# Motion_Controller.net
KiCad netlist of a schematic drawn in Altium Designer
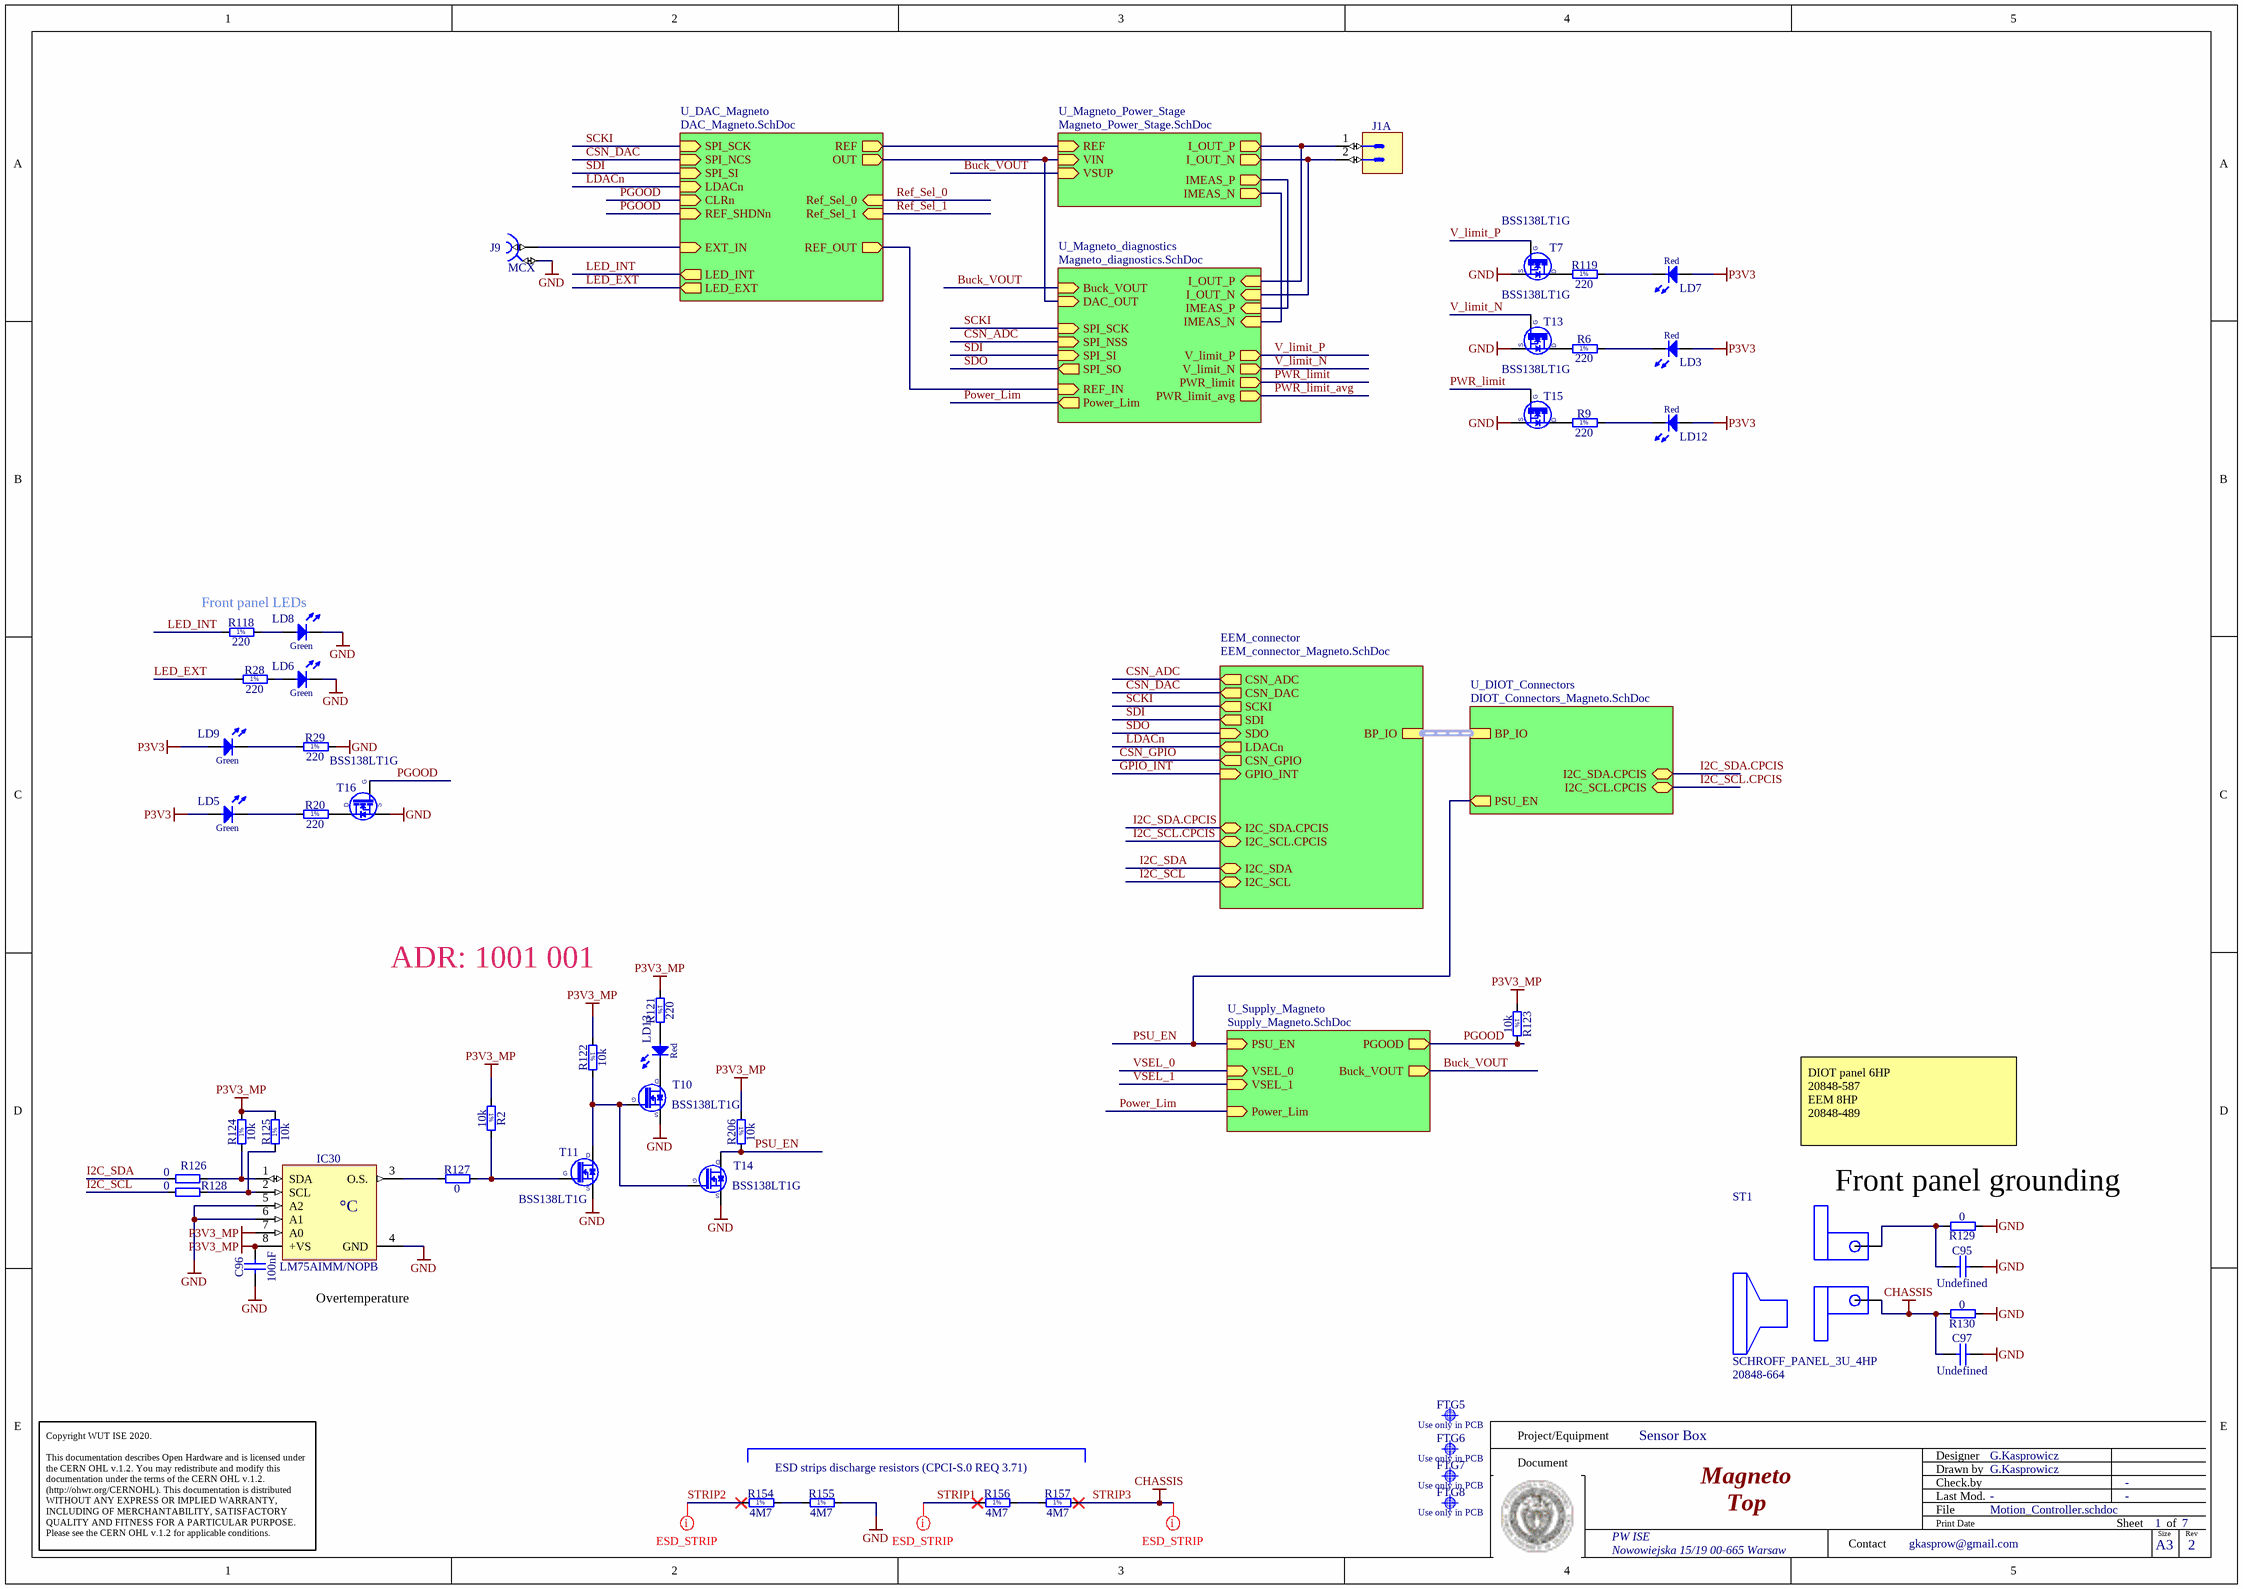
[diagram p0: Motion_Controller.schdoc]

(export (version "E")
  (design (tool "Eeschema 10.0.6"))
  (components
    (comp (ref "C95")
      (value "Undefined")
      (footprint "CAPC2012X135N")
      (description "Non-polarised capacitor")
      (fields (field (name "PART NUMBER") "CC0805_NO-VALUE") (field (name "AUTHOR") "CERN DEM JLC"))
      (libsource (lib "Capacitors") (part "Capacitor - non polarized"))
    )
    (comp (ref "C96")
      (value "100nF")
      (footprint "CAPC1005X55N")
      (description "Non-polarised capacitor")
      (fields
        (field (name "PART NUMBER") "CC0402_100NF_16V_10%_X5R")
        (field (name "VOLTAGE") "16V")
        (field (name "AUTHOR") "CERN DEM JLC")
      )
      (libsource (lib "Capacitors") (part "Capacitor - non polarized"))
    )
    (comp (ref "C97")
      (value "Undefined")
      (footprint "CAPC2012X135N")
      (description "Non-polarised capacitor")
      (fields (field (name "PART NUMBER") "CC0805_NO-VALUE") (field (name "AUTHOR") "CERN DEM JLC"))
      (libsource (lib "Capacitors") (part "Capacitor - non polarized"))
    )
    (comp (ref "FTG5")
      (value "Use only in PCB")
      (footprint "FIDUCIAL_TOP_C100-200")
      (description "Fiducial Target")
      (fields (field (name "PART NUMBER") "FIDUCIAL_TARGET_C100-200") (field (name "AUTHOR") "CERN DEM JLC"))
      (libsource (lib "Eletro-mechanical") (part "Fiducial Target"))
    )
    (comp (ref "FTG6")
      (value "Use only in PCB")
      (footprint "FIDUCIAL_TOP_S100-200")
      (description "Fiducial Target")
      (fields (field (name "PART NUMBER") "FIDUCIAL_TARGET_S100-200") (field (name "AUTHOR") "CERN DEM JLC"))
      (libsource (lib "Eletro-mechanical") (part "Fiducial Target"))
    )
    (comp (ref "FTG7")
      (value "Use only in PCB")
      (footprint "FIDUCIAL_TOP_S100-200")
      (description "Fiducial Target")
      (fields (field (name "PART NUMBER") "FIDUCIAL_TARGET_S100-200") (field (name "AUTHOR") "CERN DEM JLC"))
      (libsource (lib "Eletro-mechanical") (part "Fiducial Target"))
    )
    (comp (ref "FTG8")
      (value "Use only in PCB")
      (footprint "FIDUCIAL_TOP_S100-200")
      (description "Fiducial Target")
      (fields (field (name "PART NUMBER") "FIDUCIAL_TARGET_S100-200") (field (name "AUTHOR") "CERN DEM JLC"))
      (libsource (lib "Eletro-mechanical") (part "Fiducial Target"))
    )
    (comp (ref "IC30")
      (value "LM75AIMM/NOPB")
      (footprint "SOP65P490X109-8N")
      (description "Digital Temperature Sensor and Thermal Watchdog with Two-Wire Interface")
      (fields (field (name "MANUFACTURER") "TEXAS INSTRUMENTS") (field (name "AUTHOR") "CERN DEM JLC"))
      (libsource (lib "ICs And Semiconductors") (part "LM75"))
    )
    (comp (ref "J1")
      (value "~")
      (footprint "PHOENIX_1817615")
      (description "Connector 2 Male+2MTG")
      (fields
        (field (name "PART NUMBER") "PHOENIX_1817615")
        (field (name "MANUFACTURER") "PHOENIX CONTACT")
        (field (name "AUTHOR") "CERN DEM BC")
      )
      (libsource (lib "Connectors") (part "Connector 2 Male+2MTG"))
    )
    (comp (ref "J9")
      (value "MCX")
      (footprint "AMPHENOL_919-383J-51A")
      (fields
        (field (name "PART NUMBER") "AMPHENOL_919-383J-51A")
        (field (name "MANUFACTURER") "AMPHENOL")
        (field (name "MANUFACTURER PART NUMBER") "919-383J-51A")
        (field (name "AUTHOR") "CERN DEM BC")
      )
      (libsource (lib "Connectors") (part "Coax_1Female_1Shield"))
    )
    (comp (ref "LD3")
      (value "Red")
      (footprint "LED_DIALIGHT_555-200")
      (description "LED Red 1C 2A")
      (fields
        (field (name "PART NUMBER") "LED_DIALIGHT_555-2001F")
        (field (name "MANUFACTURER") "DIALIGHT")
        (field (name "AUTHOR") "CERN DEM JMW")
      )
      (libsource (lib "ICs And Semiconductors") (part "LED Red 1C 2A"))
    )
    (comp (ref "LD5")
      (value "Green")
      (footprint "LED_DIALIGHT_555-230")
      (description "LED Green 1C 2A")
      (fields
        (field (name "PART NUMBER") "LED_DIALIGHT_555-2301F")
        (field (name "MANUFACTURER") "DIALIGHT")
        (field (name "AUTHOR") "CERN DEM JMW")
      )
      (libsource (lib "ICs And Semiconductors") (part "LED Green 1C 2A"))
    )
    (comp (ref "LD6")
      (value "Green")
      (footprint "LED_DIALIGHT_555-230")
      (description "LED Green 1C 2A")
      (fields
        (field (name "PART NUMBER") "LED_DIALIGHT_555-2301F")
        (field (name "MANUFACTURER") "DIALIGHT")
        (field (name "AUTHOR") "CERN DEM JMW")
      )
      (libsource (lib "ICs And Semiconductors") (part "LED Green 1C 2A"))
    )
    (comp (ref "LD7")
      (value "Red")
      (footprint "LED_DIALIGHT_555-200")
      (description "LED Red 1C 2A")
      (fields
        (field (name "PART NUMBER") "LED_DIALIGHT_555-2001F")
        (field (name "MANUFACTURER") "DIALIGHT")
        (field (name "AUTHOR") "CERN DEM JMW")
      )
      (libsource (lib "ICs And Semiconductors") (part "LED Red 1C 2A"))
    )
    (comp (ref "LD8")
      (value "Green")
      (footprint "LED_DIALIGHT_555-230")
      (description "LED Green 1C 2A")
      (fields
        (field (name "PART NUMBER") "LED_DIALIGHT_555-2301F")
        (field (name "MANUFACTURER") "DIALIGHT")
        (field (name "AUTHOR") "CERN DEM JMW")
      )
      (libsource (lib "ICs And Semiconductors") (part "LED Green 1C 2A"))
    )
    (comp (ref "LD9")
      (value "Green")
      (footprint "LED_DIALIGHT_555-230")
      (description "LED Green 1C 2A")
      (fields
        (field (name "PART NUMBER") "LED_DIALIGHT_555-2301F")
        (field (name "MANUFACTURER") "DIALIGHT")
        (field (name "AUTHOR") "CERN DEM JMW")
      )
      (libsource (lib "ICs And Semiconductors") (part "LED Green 1C 2A"))
    )
    (comp (ref "LD12")
      (value "Red")
      (footprint "LED_DIALIGHT_555-200")
      (description "LED Red 1C 2A")
      (fields
        (field (name "PART NUMBER") "LED_DIALIGHT_555-2001F")
        (field (name "MANUFACTURER") "DIALIGHT")
        (field (name "AUTHOR") "CERN DEM JMW")
      )
      (libsource (lib "ICs And Semiconductors") (part "LED Red 1C 2A"))
    )
    (comp (ref "LD13")
      (value "Red")
      (footprint "LED_DIALIGHT_555-200")
      (description "LED Red 1C 2A")
      (fields
        (field (name "PART NUMBER") "LED_DIALIGHT_555-2001F")
        (field (name "MANUFACTURER") "DIALIGHT")
        (field (name "AUTHOR") "CERN DEM JMW")
      )
      (libsource (lib "ICs And Semiconductors") (part "LED Red 1C 2A"))
    )
    (comp (ref "R2")
      (value "10k")
      (footprint "RESC1005X40N")
      (description "Resistor - 1%")
      (fields
        (field (name "PART NUMBER") "R0402_10K_1%_0.0625W_100PPM")
        (field (name "POWER") "0.0625W")
        (field (name "AUTHOR") "CERN DEM JLC")
      )
      (libsource (lib "Resistors") (part "Resistor - 1%"))
    )
    (comp (ref "R6")
      (value "220")
      (footprint "RESC1608X55N")
      (description "Resistor - 1%")
      (fields
        (field (name "PART NUMBER") "R0603_220R_1%_0.1W_100PPM")
        (field (name "POWER") "0.1W")
        (field (name "AUTHOR") "CERN DEM JLC")
      )
      (libsource (lib "Resistors") (part "Resistor - 1%"))
    )
    (comp (ref "R9")
      (value "220")
      (footprint "RESC1608X55N")
      (description "Resistor - 1%")
      (fields
        (field (name "PART NUMBER") "R0603_220R_1%_0.1W_100PPM")
        (field (name "POWER") "0.1W")
        (field (name "AUTHOR") "CERN DEM JLC")
      )
      (libsource (lib "Resistors") (part "Resistor - 1%"))
    )
    (comp (ref "R20")
      (value "220")
      (footprint "RESC1608X55N")
      (description "Resistor - 1%")
      (fields
        (field (name "PART NUMBER") "R0603_220R_1%_0.1W_100PPM")
        (field (name "POWER") "0.1W")
        (field (name "AUTHOR") "CERN DEM JLC")
      )
      (libsource (lib "Resistors") (part "Resistor - 1%"))
    )
    (comp (ref "R28")
      (value "220")
      (footprint "RESC1608X55N")
      (description "Resistor - 1%")
      (fields
        (field (name "PART NUMBER") "R0603_220R_1%_0.1W_100PPM")
        (field (name "POWER") "0.1W")
        (field (name "AUTHOR") "CERN DEM JLC")
      )
      (libsource (lib "Resistors") (part "Resistor - 1%"))
    )
    (comp (ref "R29")
      (value "220")
      (footprint "RESC1608X55N")
      (description "Resistor - 1%")
      (fields
        (field (name "PART NUMBER") "R0603_220R_1%_0.1W_100PPM")
        (field (name "POWER") "0.1W")
        (field (name "AUTHOR") "CERN DEM JLC")
      )
      (libsource (lib "Resistors") (part "Resistor - 1%"))
    )
    (comp (ref "R118")
      (value "220")
      (footprint "RESC1608X55N")
      (description "Resistor - 1%")
      (fields
        (field (name "PART NUMBER") "R0603_220R_1%_0.1W_100PPM")
        (field (name "POWER") "0.1W")
        (field (name "AUTHOR") "CERN DEM JLC")
      )
      (libsource (lib "Resistors") (part "Resistor - 1%"))
    )
    (comp (ref "R119")
      (value "220")
      (footprint "RESC1608X55N")
      (description "Resistor - 1%")
      (fields
        (field (name "PART NUMBER") "R0603_220R_1%_0.1W_100PPM")
        (field (name "POWER") "0.1W")
        (field (name "AUTHOR") "CERN DEM JLC")
      )
      (libsource (lib "Resistors") (part "Resistor - 1%"))
    )
    (comp (ref "R121")
      (value "220")
      (footprint "RESC1608X55N")
      (description "Resistor - 1%")
      (fields
        (field (name "PART NUMBER") "R0603_220R_1%_0.1W_100PPM")
        (field (name "POWER") "0.1W")
        (field (name "AUTHOR") "CERN DEM JLC")
      )
      (libsource (lib "Resistors") (part "Resistor - 1%"))
    )
    (comp (ref "R122")
      (value "10k")
      (footprint "RESC1005X40N")
      (description "Resistor - 1%")
      (fields
        (field (name "PART NUMBER") "R0402_10K_1%_0.0625W_100PPM")
        (field (name "POWER") "0.0625W")
        (field (name "AUTHOR") "CERN DEM JLC")
      )
      (libsource (lib "Resistors") (part "Resistor - 1%"))
    )
    (comp (ref "R123")
      (value "10k")
      (footprint "RESC1005X40N")
      (description "Resistor - 1%")
      (fields
        (field (name "PART NUMBER") "R0402_10K_1%_0.0625W_100PPM")
        (field (name "POWER") "0.0625W")
        (field (name "AUTHOR") "CERN DEM JLC")
      )
      (libsource (lib "Resistors") (part "Resistor - 1%"))
    )
    (comp (ref "R124")
      (value "10k")
      (footprint "RESC1005X40N")
      (description "Resistor - 1%")
      (fields
        (field (name "PART NUMBER") "R0402_10K_1%_0.0625W_100PPM")
        (field (name "POWER") "0.0625W")
        (field (name "AUTHOR") "CERN DEM JLC")
      )
      (libsource (lib "Resistors") (part "Resistor - 1%"))
    )
    (comp (ref "R125")
      (value "10k")
      (footprint "RESC1005X40N")
      (description "Resistor - 1%")
      (fields
        (field (name "PART NUMBER") "R0402_10K_1%_0.0625W_100PPM")
        (field (name "POWER") "0.0625W")
        (field (name "AUTHOR") "CERN DEM JLC")
      )
      (libsource (lib "Resistors") (part "Resistor - 1%"))
    )
    (comp (ref "R126")
      (value "0")
      (footprint "RESC1005X40N")
      (description "Resistor")
      (fields
        (field (name "PART NUMBER") "R0402_0R_JUMPER")
        (field (name "MANUFACTURER") "GENERIC")
        (field (name "AUTHOR") "CERN DEM JLC")
      )
      (libsource (lib "Resistors") (part "Resistor"))
    )
    (comp (ref "R127")
      (value "0")
      (footprint "RESC1005X40N")
      (description "Resistor")
      (fields
        (field (name "PART NUMBER") "R0402_0R_JUMPER")
        (field (name "MANUFACTURER") "GENERIC")
        (field (name "AUTHOR") "CERN DEM JLC")
      )
      (libsource (lib "Resistors") (part "Resistor"))
    )
    (comp (ref "R128")
      (value "0")
      (footprint "RESC1005X40N")
      (description "Resistor")
      (fields
        (field (name "PART NUMBER") "R0402_0R_JUMPER")
        (field (name "MANUFACTURER") "GENERIC")
        (field (name "AUTHOR") "CERN DEM JLC")
      )
      (libsource (lib "Resistors") (part "Resistor"))
    )
    (comp (ref "R129")
      (value "0")
      (footprint "RESC1608X55N")
      (description "Resistor")
      (fields
        (field (name "PART NUMBER") "R0603_0R_JUMPER")
        (field (name "MANUFACTURER") "GENERIC")
        (field (name "AUTHOR") "CERN DEM JLC")
      )
      (libsource (lib "Resistors") (part "Resistor"))
    )
    (comp (ref "R130")
      (value "0")
      (footprint "RESC1608X55N")
      (description "Resistor")
      (fields
        (field (name "PART NUMBER") "R0603_0R_JUMPER")
        (field (name "MANUFACTURER") "GENERIC")
        (field (name "AUTHOR") "CERN DEM JLC")
      )
      (libsource (lib "Resistors") (part "Resistor"))
    )
    (comp (ref "R154")
      (value "4M7")
      (footprint "RESC2113X55N")
      (description "Resistor - 1%")
      (fields
        (field (name "PART NUMBER") "R0805_4M7_1%_0.125W_100PPM_VISHAY_CRCW e3")
        (field (name "POWER") "0.125W")
        (field (name "AUTHOR") "CERN DEM BR")
      )
      (libsource (lib "Resistors") (part "Resistor - 1%"))
    )
    (comp (ref "R155")
      (value "4M7")
      (footprint "RESC2113X55N")
      (description "Resistor - 1%")
      (fields
        (field (name "PART NUMBER") "R0805_4M7_1%_0.125W_100PPM_VISHAY_CRCW e3")
        (field (name "POWER") "0.125W")
        (field (name "AUTHOR") "CERN DEM BR")
      )
      (libsource (lib "Resistors") (part "Resistor - 1%"))
    )
    (comp (ref "R156")
      (value "4M7")
      (footprint "RESC2113X55N")
      (description "Resistor - 1%")
      (fields
        (field (name "PART NUMBER") "R0805_4M7_1%_0.125W_100PPM_VISHAY_CRCW e3")
        (field (name "POWER") "0.125W")
        (field (name "AUTHOR") "CERN DEM BR")
      )
      (libsource (lib "Resistors") (part "Resistor - 1%"))
    )
    (comp (ref "R157")
      (value "4M7")
      (footprint "RESC2113X55N")
      (description "Resistor - 1%")
      (fields
        (field (name "PART NUMBER") "R0805_4M7_1%_0.125W_100PPM_VISHAY_CRCW e3")
        (field (name "POWER") "0.125W")
        (field (name "AUTHOR") "CERN DEM BR")
      )
      (libsource (lib "Resistors") (part "Resistor - 1%"))
    )
    (comp (ref "R206")
      (value "10k")
      (footprint "RESC1005X40N")
      (description "Resistor - 1%")
      (fields
        (field (name "PART NUMBER") "R0402_10K_1%_0.0625W_100PPM")
        (field (name "POWER") "0.0625W")
        (field (name "AUTHOR") "CERN DEM JLC")
      )
      (libsource (lib "Resistors") (part "Resistor - 1%"))
    )
    (comp (ref "ST1")
      (value "SCHROFF_PANEL_3U_4HP")
      (footprint "SCHROFF_PANEL_3HP_4U")
      (description "Schroff 3HP 4U EUROCARD Panel Kit")
      (fields
        (field (name "MANUFACTURER") "Schroff")
        (field (name "MANUFACTURER PART NUMBER") "20818-017")
        (field (name "MANUFACTURER PART NUMBER 2") "20848-664")
      )
      (libsource (lib "Mechanical") (part "SCHROFF_PANEL_3U_4HP"))
    )
    (comp (ref "T7")
      (value "BSS138LT1G")
      (footprint "SOT95P240X110-3N")
      (description "N-CHANNEL MOSFET WITH DIODE")
      (fields (field (name "MANUFACTURER") "ON SEMICONDUCTOR") (field (name "AUTHOR") "CERN DEM JLC"))
      (libsource (lib "") (part "N-MOSFET-D 1G 2S 3D_1"))
    )
    (comp (ref "T10")
      (value "BSS138LT1G")
      (footprint "SOT95P240X110-3N")
      (description "N-CHANNEL MOSFET WITH DIODE")
      (fields (field (name "MANUFACTURER") "ON SEMICONDUCTOR") (field (name "AUTHOR") "CERN DEM JLC"))
      (libsource (lib "") (part "N-MOSFET-D 1G 2S 3D_2"))
    )
    (comp (ref "T11")
      (value "BSS138LT1G")
      (footprint "SOT95P240X110-3N")
      (description "N-CHANNEL MOSFET WITH DIODE")
      (fields (field (name "MANUFACTURER") "ON SEMICONDUCTOR") (field (name "AUTHOR") "CERN DEM JLC"))
      (libsource (lib "ICs And Semiconductors") (part "N-MOSFET-D 1G 2S 3D"))
    )
    (comp (ref "T13")
      (value "BSS138LT1G")
      (footprint "SOT95P240X110-3N")
      (description "N-CHANNEL MOSFET WITH DIODE")
      (fields (field (name "MANUFACTURER") "ON SEMICONDUCTOR") (field (name "AUTHOR") "CERN DEM JLC"))
      (libsource (lib "") (part "N-MOSFET-D 1G 2S 3D_1"))
    )
    (comp (ref "T14")
      (value "BSS138LT1G")
      (footprint "SOT95P240X110-3N")
      (description "N-CHANNEL MOSFET WITH DIODE")
      (fields (field (name "MANUFACTURER") "ON SEMICONDUCTOR") (field (name "AUTHOR") "CERN DEM JLC"))
      (libsource (lib "") (part "N-MOSFET-D 1G 2S 3D_2"))
    )
    (comp (ref "T15")
      (value "BSS138LT1G")
      (footprint "SOT95P240X110-3N")
      (description "N-CHANNEL MOSFET WITH DIODE")
      (fields (field (name "MANUFACTURER") "ON SEMICONDUCTOR") (field (name "AUTHOR") "CERN DEM JLC"))
      (libsource (lib "") (part "N-MOSFET-D 1G 2S 3D_1"))
    )
    (comp (ref "T16")
      (value "BSS138LT1G")
      (footprint "SOT95P240X110-3N")
      (description "N-CHANNEL MOSFET WITH DIODE")
      (fields (field (name "MANUFACTURER") "ON SEMICONDUCTOR") (field (name "AUTHOR") "CERN DEM JLC"))
      (libsource (lib "") (part "N-MOSFET-D 1G 2S 3D_3"))
    )
  )
  (nets
    (net (code "6") (name "/EXT_IN") (class "Default")
      (node (ref "J9") (pin "1") (pinfunction "1_1") (pintype "bidirectional"))
    )
    (net (code "8") (name "/I2C_SCL") (class "Default")
      (node (ref "R128") (pin "1") (pinfunction "1_1") (pintype "passive"))
    )
    (net (code "10") (name "/I2C_SDA") (class "Default")
      (node (ref "R126") (pin "1") (pinfunction "1_1") (pintype "passive"))
    )
    (net (code "14") (name "/I_OUT_N") (class "Default")
      (node (ref "J1") (pin "2") (pinfunction "2_2") (pintype "bidirectional"))
    )
    (net (code "15") (name "/I_OUT_P") (class "Default")
      (node (ref "J1") (pin "1") (pinfunction "1_1") (pintype "bidirectional"))
    )
    (net (code "17") (name "/LED_EXT") (class "Default")
      (node (ref "R28") (pin "1") (pinfunction "1_1") (pintype "passive"))
    )
    (net (code "18") (name "/LED_INT") (class "Default")
      (node (ref "R118") (pin "1") (pinfunction "1_1") (pintype "passive"))
    )
    (net (code "20") (name "/PGOOD") (class "Default")
      (node (ref "R123") (pin "2") (pinfunction "2_2") (pintype "passive"))
      (node (ref "T16") (pin "1") (pinfunction "G_1") (pintype "passive"))
    )
    (net (code "21") (name "/PSU_EN") (class "Default")
      (node (ref "R206") (pin "2") (pinfunction "2_2") (pintype "passive"))
      (node (ref "T14") (pin "3") (pinfunction "D_3") (pintype "passive"))
    )
    (net (code "22") (name "/PWR_limit") (class "Default")
      (node (ref "T15") (pin "1") (pinfunction "G_1") (pintype "passive"))
    )
    (net (code "32") (name "/STRIP1") (class "Default")
      (node (ref "R156") (pin "1") (pinfunction "1_1") (pintype "passive+no_connect"))
    )
    (net (code "33") (name "/STRIP2") (class "Default")
      (node (ref "R154") (pin "1") (pinfunction "1_1") (pintype "passive+no_connect"))
    )
    (net (code "36") (name "/V_limit_N") (class "Default")
      (node (ref "T13") (pin "1") (pinfunction "G_1") (pintype "passive"))
    )
    (net (code "37") (name "/V_limit_P") (class "Default")
      (node (ref "T7") (pin "1") (pinfunction "G_1") (pintype "passive"))
    )
    (net (code "38") (name "CHASSIS") (class "Default")
      (node (ref "C97") (pin "1") (pinfunction "1_1") (pintype "passive"))
      (node (ref "R130") (pin "2") (pinfunction "2_2") (pintype "passive"))
      (node (ref "R157") (pin "2") (pinfunction "2_2") (pintype "passive"))
      (node (ref "ST1") (pin "0") (pinfunction "0_0") (pintype "passive"))
    )
    (net (code "39") (name "GND") (class "Default")
      (node (ref "C95") (pin "2") (pinfunction "2_2") (pintype "passive"))
      (node (ref "C96") (pin "1") (pinfunction "1_1") (pintype "passive"))
      (node (ref "C97") (pin "2") (pinfunction "2_2") (pintype "passive"))
      (node (ref "IC30") (pin "4") (pinfunction "GND_4") (pintype "power_in"))
      (node (ref "IC30") (pin "5") (pinfunction "A2_5") (pintype "input"))
      (node (ref "IC30") (pin "6") (pinfunction "A1_6") (pintype "input"))
      (node (ref "J9") (pin "2") (pinfunction "2_2") (pintype "bidirectional"))
      (node (ref "LD6") (pin "1") (pinfunction "C_1") (pintype "passive"))
      (node (ref "LD8") (pin "1") (pinfunction "C_1") (pintype "passive"))
      (node (ref "R129") (pin "1") (pinfunction "1_1") (pintype "passive"))
      (node (ref "R130") (pin "1") (pinfunction "1_1") (pintype "passive"))
      (node (ref "R155") (pin "2") (pinfunction "2_2") (pintype "passive"))
      (node (ref "R29") (pin "2") (pinfunction "2_2") (pintype "passive"))
      (node (ref "T10") (pin "2") (pinfunction "S_2") (pintype "passive"))
      (node (ref "T11") (pin "2") (pinfunction "S_2") (pintype "passive"))
      (node (ref "T13") (pin "2") (pinfunction "S_2") (pintype "passive"))
      (node (ref "T14") (pin "2") (pinfunction "S_2") (pintype "passive"))
      (node (ref "T15") (pin "2") (pinfunction "S_2") (pintype "passive"))
      (node (ref "T16") (pin "2") (pinfunction "S_2") (pintype "passive"))
      (node (ref "T7") (pin "2") (pinfunction "S_2") (pintype "passive"))
    )
    (net (code "40") (name "Net-(C95-Pad1)") (class "Default")
      (node (ref "C95") (pin "1") (pinfunction "1_1") (pintype "passive"))
      (node (ref "R129") (pin "2") (pinfunction "2_2") (pintype "passive"))
      (node (ref "ST1") (pin "1") (pinfunction "1_1") (pintype "passive"))
    )
    (net (code "41") (name "Net-(IC30-O.S.)") (class "Default")
      (node (ref "IC30") (pin "3") (pinfunction "O.S._3") (pintype "output"))
      (node (ref "R127") (pin "1") (pinfunction "1_1") (pintype "passive"))
    )
    (net (code "42") (name "Net-(IC30-SCL)") (class "Default")
      (node (ref "IC30") (pin "2") (pinfunction "SCL_2") (pintype "input"))
      (node (ref "R125") (pin "1") (pinfunction "1_1") (pintype "passive"))
      (node (ref "R128") (pin "2") (pinfunction "2_2") (pintype "passive"))
    )
    (net (code "43") (name "Net-(IC30-SDA)") (class "Default")
      (node (ref "IC30") (pin "1") (pinfunction "SDA_1") (pintype "bidirectional"))
      (node (ref "R124") (pin "1") (pinfunction "1_1") (pintype "passive"))
      (node (ref "R126") (pin "2") (pinfunction "2_2") (pintype "passive"))
    )
    (net (code "44") (name "Net-(LD3-C)") (class "Default")
      (node (ref "LD3") (pin "1") (pinfunction "C_1") (pintype "passive"))
      (node (ref "R6") (pin "1") (pinfunction "1_1") (pintype "passive"))
    )
    (net (code "45") (name "Net-(LD5-C)") (class "Default")
      (node (ref "LD5") (pin "1") (pinfunction "C_1") (pintype "passive"))
      (node (ref "R20") (pin "1") (pinfunction "1_1") (pintype "passive"))
    )
    (net (code "46") (name "Net-(LD6-A)") (class "Default")
      (node (ref "LD6") (pin "2") (pinfunction "A_2") (pintype "passive"))
      (node (ref "R28") (pin "2") (pinfunction "2_2") (pintype "passive"))
    )
    (net (code "47") (name "Net-(LD7-C)") (class "Default")
      (node (ref "LD7") (pin "1") (pinfunction "C_1") (pintype "passive"))
      (node (ref "R119") (pin "1") (pinfunction "1_1") (pintype "passive"))
    )
    (net (code "48") (name "Net-(LD8-A)") (class "Default")
      (node (ref "LD8") (pin "2") (pinfunction "A_2") (pintype "passive"))
      (node (ref "R118") (pin "2") (pinfunction "2_2") (pintype "passive"))
    )
    (net (code "49") (name "Net-(LD9-C)") (class "Default")
      (node (ref "LD9") (pin "1") (pinfunction "C_1") (pintype "passive"))
      (node (ref "R29") (pin "1") (pinfunction "1_1") (pintype "passive"))
    )
    (net (code "50") (name "Net-(LD12-C)") (class "Default")
      (node (ref "LD12") (pin "1") (pinfunction "C_1") (pintype "passive"))
      (node (ref "R9") (pin "1") (pinfunction "1_1") (pintype "passive"))
    )
    (net (code "51") (name "Net-(LD13-A)") (class "Default")
      (node (ref "LD13") (pin "2") (pinfunction "A_2") (pintype "passive"))
      (node (ref "R121") (pin "2") (pinfunction "2_2") (pintype "passive"))
    )
    (net (code "52") (name "Net-(LD13-C)") (class "Default")
      (node (ref "LD13") (pin "1") (pinfunction "C_1") (pintype "passive"))
      (node (ref "T10") (pin "3") (pinfunction "D_3") (pintype "passive"))
    )
    (net (code "53") (name "Net-(R154-Pad2)") (class "Default")
      (node (ref "R154") (pin "2") (pinfunction "2_2") (pintype "passive"))
      (node (ref "R155") (pin "1") (pinfunction "1_1") (pintype "passive"))
    )
    (net (code "54") (name "Net-(R156-Pad2)") (class "Default")
      (node (ref "R156") (pin "2") (pinfunction "2_2") (pintype "passive"))
      (node (ref "R157") (pin "1") (pinfunction "1_1") (pintype "passive"))
    )
    (net (code "55") (name "Net-(T7-D)") (class "Default")
      (node (ref "R119") (pin "2") (pinfunction "2_2") (pintype "passive"))
      (node (ref "T7") (pin "3") (pinfunction "D_3") (pintype "passive"))
    )
    (net (code "56") (name "Net-(T10-G)") (class "Default")
      (node (ref "R122") (pin "2") (pinfunction "2_2") (pintype "passive"))
      (node (ref "T10") (pin "1") (pinfunction "G_1") (pintype "passive"))
      (node (ref "T11") (pin "3") (pinfunction "D_3") (pintype "passive"))
      (node (ref "T14") (pin "1") (pinfunction "G_1") (pintype "passive"))
    )
    (net (code "57") (name "Net-(T11-G)") (class "Default")
      (node (ref "R127") (pin "2") (pinfunction "2_2") (pintype "passive"))
      (node (ref "R2") (pin "2") (pinfunction "2_2") (pintype "passive"))
      (node (ref "T11") (pin "1") (pinfunction "G_1") (pintype "passive"))
    )
    (net (code "58") (name "Net-(T13-D)") (class "Default")
      (node (ref "R6") (pin "2") (pinfunction "2_2") (pintype "passive"))
      (node (ref "T13") (pin "3") (pinfunction "D_3") (pintype "passive"))
    )
    (net (code "59") (name "Net-(T15-D)") (class "Default")
      (node (ref "R9") (pin "2") (pinfunction "2_2") (pintype "passive"))
      (node (ref "T15") (pin "3") (pinfunction "D_3") (pintype "passive"))
    )
    (net (code "60") (name "Net-(T16-D)") (class "Default")
      (node (ref "R20") (pin "2") (pinfunction "2_2") (pintype "passive"))
      (node (ref "T16") (pin "3") (pinfunction "D_3") (pintype "passive"))
    )
    (net (code "61") (name "P3V3") (class "Default")
      (node (ref "LD12") (pin "2") (pinfunction "A_2") (pintype "passive"))
      (node (ref "LD3") (pin "2") (pinfunction "A_2") (pintype "passive"))
      (node (ref "LD5") (pin "2") (pinfunction "A_2") (pintype "passive"))
      (node (ref "LD7") (pin "2") (pinfunction "A_2") (pintype "passive"))
      (node (ref "LD9") (pin "2") (pinfunction "A_2") (pintype "passive"))
    )
    (net (code "62") (name "P3V3_MP") (class "Default")
      (node (ref "C96") (pin "2") (pinfunction "2_2") (pintype "passive"))
      (node (ref "IC30") (pin "7") (pinfunction "A0_7") (pintype "input"))
      (node (ref "IC30") (pin "8") (pinfunction "+VS_8") (pintype "power_in"))
      (node (ref "R121") (pin "1") (pinfunction "1_1") (pintype "passive"))
      (node (ref "R122") (pin "1") (pinfunction "1_1") (pintype "passive"))
      (node (ref "R123") (pin "1") (pinfunction "1_1") (pintype "passive"))
      (node (ref "R124") (pin "2") (pinfunction "2_2") (pintype "passive"))
      (node (ref "R125") (pin "2") (pinfunction "2_2") (pintype "passive"))
      (node (ref "R2") (pin "1") (pinfunction "1_1") (pintype "passive"))
      (node (ref "R206") (pin "1") (pinfunction "1_1") (pintype "passive"))
    )
  )
)
